# USB2.net
KiCad netlist of a schematic drawn in Altium Designer
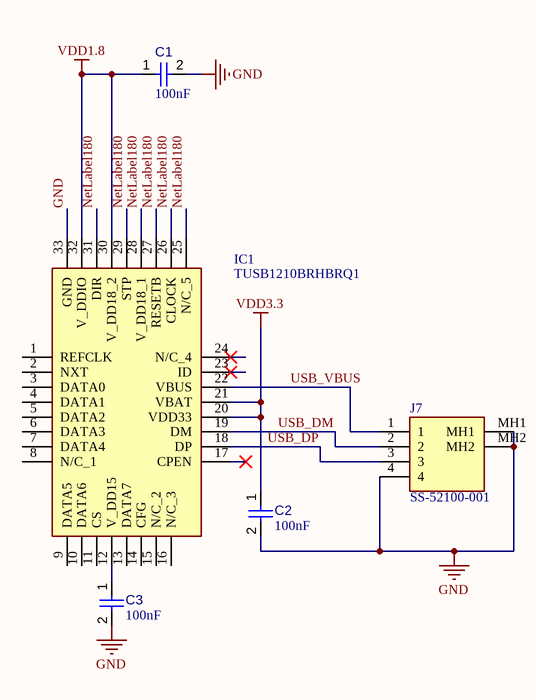
[diagram p0: USB2.SchDoc]

(export (version "E")
  (design (tool "Eeschema 10.0.6"))
  (components
    (comp (ref "C1")
      (value "100nF")
      (footprint "CAPC0402(1005)60_L")
      (description "Chip Capacitor, 100nF +/-20%, 25V, 0402, Thickness 0.6 mm")
      (fields (field (name "TOLERANCE") "10%") (field (name "Comment") "Capacitor 100nF +/-20% 25V 0402"))
      (libsource (lib "Stephen Barlett") (part "CAP-NP-2"))
    )
    (comp (ref "C2")
      (value "100nF")
      (footprint "CAPC0402(1005)60_L")
      (description "Chip Capacitor, 100nF +/-20%, 25V, 0402, Thickness 0.6 mm")
      (fields (field (name "TOLERANCE") "10%") (field (name "Comment") "Capacitor 100nF +/-20% 25V 0402"))
      (libsource (lib "Stephen Barlett") (part "CAP-NP-2"))
    )
    (comp (ref "C3")
      (value "100nF")
      (footprint "CAPC0402(1005)60_L")
      (description "Chip Capacitor, 100nF +/-20%, 25V, 0402, Thickness 0.6 mm")
      (fields (field (name "TOLERANCE") "10%") (field (name "Comment") "Capacitor 100nF +/-20% 25V 0402"))
      (libsource (lib "Stephen Barlett") (part "CAP-NP-2"))
    )
    (comp (ref "IC1")
      (value "TUSB1210BRHBRQ1")
      (footprint "SamacSys:QFN50P500X500X100-33N-D")
      (description "Integrated Circuit")
      (fields (field (name "MOUSER PART NUMBER") "595-TUSB1210BRHBRQ1"))
      (libsource (lib "*") (part "TUSB1210BRHBRQ1"))
    )
    (comp (ref "J7")
      (value "SS-52100-001")
      (footprint "SamacSys:SS52100001")
      (description "Connector")
      (fields (field (name "MOUSER PART NUMBER") "530-SS-52100-001"))
      (libsource (lib "*") (part "SS-52100-001"))
    )
  )
  (nets
    (net (code "1") (name "/NetLabel180") (class "Default")
      (node (ref "IC1") (pin "25") (pinfunction "N/C_5_25") (pintype "passive"))
      (node (ref "IC1") (pin "26") (pinfunction "CLOCK_26") (pintype "passive"))
      (node (ref "IC1") (pin "27") (pinfunction "RESETB_27") (pintype "passive"))
      (node (ref "IC1") (pin "28") (pinfunction "V_DD18_1_28") (pintype "passive"))
      (node (ref "IC1") (pin "29") (pinfunction "STP_29") (pintype "passive"))
      (node (ref "IC1") (pin "31") (pinfunction "DIR_31") (pintype "passive"))
    )
    (net (code "2") (name "/USB_DM") (class "Default")
      (node (ref "IC1") (pin "19") (pinfunction "DM_19") (pintype "passive"))
      (node (ref "J7") (pin "2") (pinfunction "2_2") (pintype "passive"))
    )
    (net (code "3") (name "/USB_DP") (class "Default")
      (node (ref "IC1") (pin "18") (pinfunction "DP_18") (pintype "passive"))
      (node (ref "J7") (pin "3") (pinfunction "3_3") (pintype "passive"))
    )
    (net (code "4") (name "/USB_VBUS") (class "Default")
      (node (ref "IC1") (pin "22") (pinfunction "VBUS_22") (pintype "passive"))
      (node (ref "J7") (pin "1") (pinfunction "1_1") (pintype "passive"))
    )
    (net (code "5") (name "GND") (class "Default")
      (node (ref "C1") (pin "2") (pinfunction "2_2") (pintype "passive"))
      (node (ref "C2") (pin "2") (pinfunction "2_2") (pintype "passive"))
      (node (ref "C3") (pin "2") (pinfunction "2_2") (pintype "passive"))
      (node (ref "IC1") (pin "33") (pinfunction "GND_33") (pintype "passive"))
      (node (ref "J7") (pin "4") (pinfunction "4_4") (pintype "passive"))
      (node (ref "J7") (pin "MH1") (pinfunction "MH1_MH1") (pintype "passive"))
      (node (ref "J7") (pin "MH2") (pinfunction "MH2_MH2") (pintype "passive"))
    )
    (net (code "6") (name "Net-(IC1-V_DD15)") (class "Default")
      (node (ref "C3") (pin "1") (pinfunction "1_1") (pintype "passive"))
      (node (ref "IC1") (pin "12") (pinfunction "V_DD15_12") (pintype "passive"))
    )
    (net (code "7") (name "VDD1.8") (class "Default")
      (node (ref "C1") (pin "1") (pinfunction "1_1") (pintype "passive"))
      (node (ref "IC1") (pin "30") (pinfunction "V_DD18_2_30") (pintype "passive"))
      (node (ref "IC1") (pin "32") (pinfunction "V_DDIO_32") (pintype "passive"))
    )
    (net (code "8") (name "VDD3.3") (class "Default")
      (node (ref "C2") (pin "1") (pinfunction "1_1") (pintype "passive"))
      (node (ref "IC1") (pin "20") (pinfunction "VDD33_20") (pintype "passive"))
      (node (ref "IC1") (pin "21") (pinfunction "VBAT_21") (pintype "passive"))
    )
    (net (code "9") (name "unconnected-(IC1-CFG-Pad14)") (class "Default")
      (node (ref "IC1") (pin "14") (pinfunction "CFG_14") (pintype "passive"))
    )
    (net (code "10") (name "unconnected-(IC1-CPEN-Pad17)") (class "Default")
      (node (ref "IC1") (pin "17") (pinfunction "CPEN_17") (pintype "passive+no_connect"))
    )
    (net (code "11") (name "unconnected-(IC1-CS-Pad11)") (class "Default")
      (node (ref "IC1") (pin "11") (pinfunction "CS_11") (pintype "passive"))
    )
    (net (code "12") (name "unconnected-(IC1-DATA0-Pad3)") (class "Default")
      (node (ref "IC1") (pin "3") (pinfunction "DATA0_3") (pintype "passive"))
    )
    (net (code "13") (name "unconnected-(IC1-DATA1-Pad4)") (class "Default")
      (node (ref "IC1") (pin "4") (pinfunction "DATA1_4") (pintype "passive"))
    )
    (net (code "14") (name "unconnected-(IC1-DATA2-Pad5)") (class "Default")
      (node (ref "IC1") (pin "5") (pinfunction "DATA2_5") (pintype "passive"))
    )
    (net (code "15") (name "unconnected-(IC1-DATA3-Pad6)") (class "Default")
      (node (ref "IC1") (pin "6") (pinfunction "DATA3_6") (pintype "passive"))
    )
    (net (code "16") (name "unconnected-(IC1-DATA4-Pad7)") (class "Default")
      (node (ref "IC1") (pin "7") (pinfunction "DATA4_7") (pintype "passive"))
    )
    (net (code "17") (name "unconnected-(IC1-DATA5-Pad9)") (class "Default")
      (node (ref "IC1") (pin "9") (pinfunction "DATA5_9") (pintype "passive"))
    )
    (net (code "18") (name "unconnected-(IC1-DATA6-Pad10)") (class "Default")
      (node (ref "IC1") (pin "10") (pinfunction "DATA6_10") (pintype "passive"))
    )
    (net (code "19") (name "unconnected-(IC1-DATA7-Pad13)") (class "Default")
      (node (ref "IC1") (pin "13") (pinfunction "DATA7_13") (pintype "passive"))
    )
    (net (code "20") (name "unconnected-(IC1-ID-Pad23)") (class "Default")
      (node (ref "IC1") (pin "23") (pinfunction "ID_23") (pintype "passive+no_connect"))
    )
    (net (code "21") (name "unconnected-(IC1-NXT-Pad2)") (class "Default")
      (node (ref "IC1") (pin "2") (pinfunction "NXT_2") (pintype "passive"))
    )
    (net (code "22") (name "unconnected-(IC1-N{slash}C_1-Pad8)") (class "Default")
      (node (ref "IC1") (pin "8") (pinfunction "N/C_1_8") (pintype "passive"))
    )
    (net (code "23") (name "unconnected-(IC1-N{slash}C_2-Pad15)") (class "Default")
      (node (ref "IC1") (pin "15") (pinfunction "N/C_2_15") (pintype "passive"))
    )
    (net (code "24") (name "unconnected-(IC1-N{slash}C_3-Pad16)") (class "Default")
      (node (ref "IC1") (pin "16") (pinfunction "N/C_3_16") (pintype "passive"))
    )
    (net (code "25") (name "unconnected-(IC1-N{slash}C_4-Pad24)") (class "Default")
      (node (ref "IC1") (pin "24") (pinfunction "N/C_4_24") (pintype "passive+no_connect"))
    )
    (net (code "26") (name "unconnected-(IC1-REFCLK-Pad1)") (class "Default")
      (node (ref "IC1") (pin "1") (pinfunction "REFCLK_1") (pintype "passive"))
    )
  )
)
